# Sheet0-mcu.net
KiCad netlist of a schematic drawn in Altium Designer
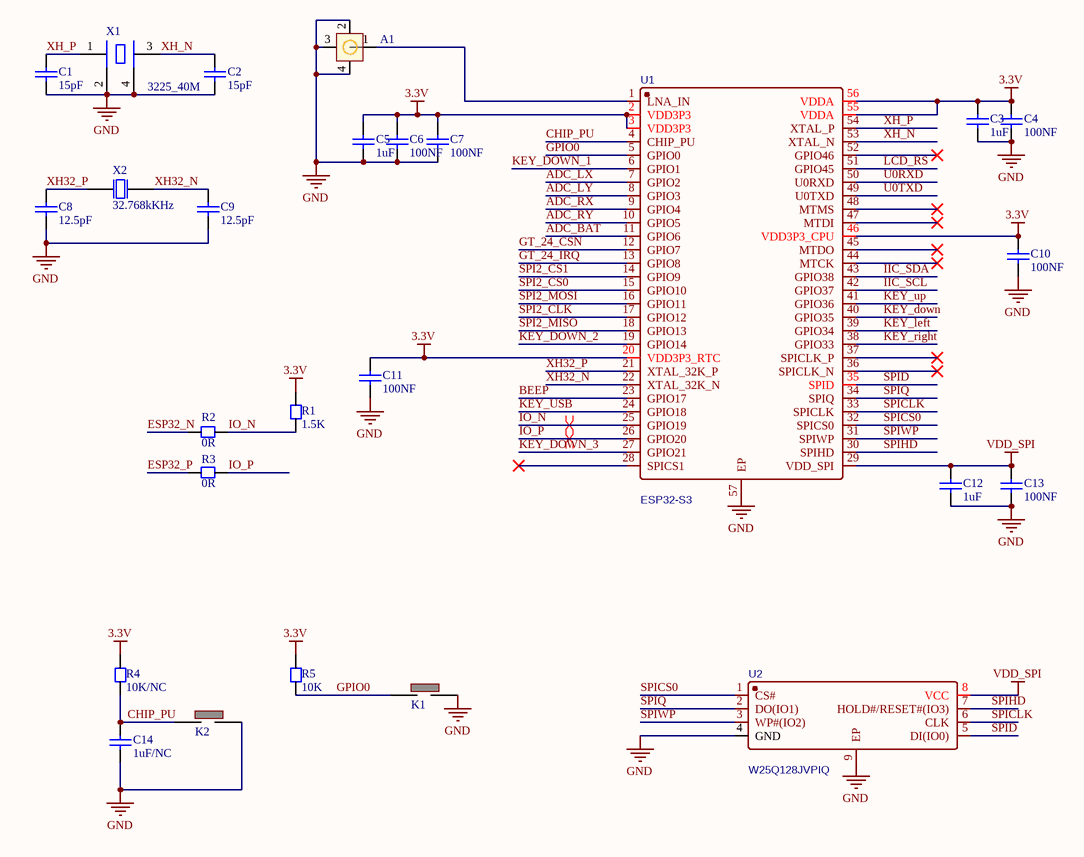
[diagram p0: Sheet0-mcu.SchDoc]

(export (version "E")
  (design (tool "Eeschema 10.0.6"))
  (components
    (comp (ref "A1")
      (value "ANT-IPEX")
      (footprint "IPEX-SMD_HC-RF-IPEX0303-01")
      (description "贴片封装的天线 封装类型为IPEX")
      (libsource (lib "antenna") (part "ANT-IPEX"))
    )
    (comp (ref "C1")
      (value "15pF")
      (footprint "CC1608-0603")
      (description "0603封装的电容")
      (fields (field (name "PUBLISHER") "Altium Limited"))
      (libsource (lib "base") (part "Cap Chip 0603"))
    )
    (comp (ref "C2")
      (value "15pF")
      (footprint "CC1608-0603")
      (description "0603封装的电容")
      (fields (field (name "PUBLISHER") "Altium Limited"))
      (libsource (lib "base") (part "Cap Chip 0603"))
    )
    (comp (ref "C3")
      (value "1uF")
      (footprint "CC1608-0603")
      (description "0603封装的电容")
      (fields (field (name "PUBLISHER") "Altium Limited"))
      (libsource (lib "base") (part "Cap Chip 0603"))
    )
    (comp (ref "C4")
      (value "100NF")
      (footprint "CC1608-0603")
      (description "0603封装的电容")
      (fields (field (name "PUBLISHER") "Altium Limited"))
      (libsource (lib "base") (part "Cap Chip 0603"))
    )
    (comp (ref "C5")
      (value "1uF")
      (footprint "CC1608-0603")
      (description "0603封装的电容")
      (fields (field (name "PUBLISHER") "Altium Limited"))
      (libsource (lib "base") (part "Cap Chip 0603"))
    )
    (comp (ref "C6")
      (value "100NF")
      (footprint "CC1608-0603")
      (description "0603封装的电容")
      (fields (field (name "PUBLISHER") "Altium Limited"))
      (libsource (lib "base") (part "Cap Chip 0603"))
    )
    (comp (ref "C7")
      (value "100NF")
      (footprint "CC1608-0603")
      (description "0603封装的电容")
      (fields (field (name "PUBLISHER") "Altium Limited"))
      (libsource (lib "base") (part "Cap Chip 0603"))
    )
    (comp (ref "C8")
      (value "12.5pF")
      (footprint "CC1608-0603")
      (description "0603封装的电容")
      (fields (field (name "PUBLISHER") "Altium Limited"))
      (libsource (lib "base") (part "Cap Chip 0603"))
    )
    (comp (ref "C9")
      (value "12.5pF")
      (footprint "CC1608-0603")
      (description "0603封装的电容")
      (fields (field (name "PUBLISHER") "Altium Limited"))
      (libsource (lib "base") (part "Cap Chip 0603"))
    )
    (comp (ref "C10")
      (value "100NF")
      (footprint "CC1608-0603")
      (description "0603封装的电容")
      (fields (field (name "PUBLISHER") "Altium Limited"))
      (libsource (lib "base") (part "Cap Chip 0603"))
    )
    (comp (ref "C11")
      (value "100NF")
      (footprint "CC1608-0603")
      (description "0603封装的电容")
      (fields (field (name "PUBLISHER") "Altium Limited"))
      (libsource (lib "base") (part "Cap Chip 0603"))
    )
    (comp (ref "C12")
      (value "1uF")
      (footprint "CC1608-0603")
      (description "0603封装的电容")
      (fields (field (name "PUBLISHER") "Altium Limited"))
      (libsource (lib "base") (part "Cap Chip 0603"))
    )
    (comp (ref "C13")
      (value "100NF")
      (footprint "CC1608-0603")
      (description "0603封装的电容")
      (fields (field (name "PUBLISHER") "Altium Limited"))
      (libsource (lib "base") (part "Cap Chip 0603"))
    )
    (comp (ref "C14")
      (value "1uF/NC")
      (footprint "CC1608-0603")
      (description "0603封装的电容")
      (fields (field (name "PUBLISHER") "Altium Limited"))
      (libsource (lib "base") (part "Cap Chip 0603"))
    )
    (comp (ref "K1")
      (value "KEY 3*4")
      (footprint "KEY 3*4")
      (description "轻触开关按键")
      (libsource (lib "base") (part "KEY 3*4"))
    )
    (comp (ref "K2")
      (value "KEY 3*4")
      (footprint "KEY 3*4")
      (description "轻触开关按键")
      (libsource (lib "base") (part "KEY 3*4"))
    )
    (comp (ref "R1")
      (value "1.5K")
      (footprint "CR1608-0603")
      (description "0603封装电阻")
      (fields (field (name "PUBLISHER") "Altium Limited"))
      (libsource (lib "") (part "Resistor Chip 0603_2"))
    )
    (comp (ref "R2")
      (value "0R")
      (footprint "CR1608-0603")
      (description "0603封装电阻")
      (fields (field (name "PUBLISHER") "Altium Limited"))
      (libsource (lib "base") (part "Resistor Chip 0603"))
    )
    (comp (ref "R3")
      (value "0R")
      (footprint "CR1608-0603")
      (description "0603封装电阻")
      (fields (field (name "PUBLISHER") "Altium Limited"))
      (libsource (lib "base") (part "Resistor Chip 0603"))
    )
    (comp (ref "R4")
      (value "10K/NC")
      (footprint "CR1608-0603")
      (description "0603封装电阻")
      (fields (field (name "PUBLISHER") "Altium Limited"))
      (libsource (lib "") (part "Resistor Chip 0603_1"))
    )
    (comp (ref "R5")
      (value "10K")
      (footprint "CR1608-0603")
      (description "0603封装电阻")
      (fields (field (name "PUBLISHER") "Altium Limited"))
      (libsource (lib "") (part "Resistor Chip 0603_1"))
    )
    (comp (ref "U1")
      (value "ESP32-S3")
      (footprint "QFN-56")
      (fields (field (name "MANUFACTURER") "ESPRESSIF(乐鑫)") (field (name "CONTRIBUTOR") "LCSC"))
      (libsource (lib "singlechip") (part "ESP32-S3"))
    )
    (comp (ref "U2")
      (value "W25Q128JVPIQ")
      (footprint "WSON-8")
      (fields (field (name "MANUFACTURER") "WINBOND(华邦)") (field (name "CONTRIBUTOR") "LCSC"))
      (libsource (lib "PB-Chip") (part "W25Q128JVPIQ"))
    )
    (comp (ref "X1")
      (value "3225_40M")
      (footprint "XTAL-3225")
      (description "3225封装的晶振")
      (libsource (lib "base") (part "XTAL 3225"))
    )
    (comp (ref "X2")
      (value "32.768kKHz")
      (footprint "XTAL-3215")
      (description "3215封装的时钟晶振")
      (libsource (lib "base") (part "XTAL 3215 32.768kKHz"))
    )
  )
  (nets
    (net (code "1") (name "/ADC_BAT") (class "Default")
      (node (ref "U1") (pin "11") (pinfunction "GPIO6_11") (pintype "passive"))
    )
    (net (code "2") (name "/ADC_LX") (class "Default")
      (node (ref "U1") (pin "7") (pinfunction "GPIO2_7") (pintype "passive"))
    )
    (net (code "3") (name "/ADC_LY") (class "Default")
      (node (ref "U1") (pin "8") (pinfunction "GPIO3_8") (pintype "passive"))
    )
    (net (code "4") (name "/ADC_RX") (class "Default")
      (node (ref "U1") (pin "9") (pinfunction "GPIO4_9") (pintype "passive"))
    )
    (net (code "5") (name "/ADC_RY") (class "Default")
      (node (ref "U1") (pin "10") (pinfunction "GPIO5_10") (pintype "passive"))
    )
    (net (code "6") (name "/BEEP") (class "Default")
      (node (ref "U1") (pin "23") (pinfunction "GPIO17_23") (pintype "passive"))
    )
    (net (code "7") (name "/CHIP_PU") (class "Default")
      (node (ref "C14") (pin "2") (pinfunction "2_2") (pintype "passive"))
      (node (ref "K2") (pin "1") (pinfunction "1_1") (pintype "passive"))
      (node (ref "R4") (pin "1") (pinfunction "1_1") (pintype "passive"))
      (node (ref "U1") (pin "4") (pinfunction "CHIP_PU_4") (pintype "passive"))
    )
    (net (code "8") (name "/ESP32_N") (class "Default")
      (node (ref "R2") (pin "2") (pinfunction "2_2") (pintype "passive"))
    )
    (net (code "9") (name "/ESP32_P") (class "Default")
      (node (ref "R3") (pin "2") (pinfunction "2_2") (pintype "passive"))
    )
    (net (code "10") (name "/GPIO0") (class "Default")
      (node (ref "K1") (pin "1") (pinfunction "1_1") (pintype "passive"))
      (node (ref "R5") (pin "1") (pinfunction "1_1") (pintype "passive"))
      (node (ref "U1") (pin "5") (pinfunction "GPIO0_5") (pintype "passive"))
    )
    (net (code "11") (name "/GT_24_CSN") (class "Default")
      (node (ref "U1") (pin "12") (pinfunction "GPIO7_12") (pintype "passive"))
    )
    (net (code "12") (name "/GT_24_IRQ") (class "Default")
      (node (ref "U1") (pin "13") (pinfunction "GPIO8_13") (pintype "passive"))
    )
    (net (code "13") (name "/IIC_SCL") (class "Default")
      (node (ref "U1") (pin "42") (pinfunction "GPIO37_42") (pintype "passive"))
    )
    (net (code "14") (name "/IIC_SDA") (class "Default")
      (node (ref "U1") (pin "43") (pinfunction "GPIO38_43") (pintype "passive"))
    )
    (net (code "15") (name "/IO_N") (class "Default")
      (node (ref "R1") (pin "2") (pinfunction "2_2") (pintype "passive"))
      (node (ref "R2") (pin "1") (pinfunction "1_1") (pintype "passive"))
      (node (ref "U1") (pin "25") (pinfunction "GPIO19_25") (pintype "passive"))
    )
    (net (code "16") (name "/IO_P") (class "Default")
      (node (ref "R3") (pin "1") (pinfunction "1_1") (pintype "passive"))
      (node (ref "U1") (pin "26") (pinfunction "GPIO20_26") (pintype "passive"))
    )
    (net (code "17") (name "/KEY_DOWN_1") (class "Default")
      (node (ref "U1") (pin "6") (pinfunction "GPIO1_6") (pintype "passive"))
    )
    (net (code "18") (name "/KEY_DOWN_2") (class "Default")
      (node (ref "U1") (pin "19") (pinfunction "GPIO14_19") (pintype "passive"))
    )
    (net (code "19") (name "/KEY_DOWN_3") (class "Default")
      (node (ref "U1") (pin "27") (pinfunction "GPIO21_27") (pintype "passive"))
    )
    (net (code "20") (name "/KEY_USB") (class "Default")
      (node (ref "U1") (pin "24") (pinfunction "GPIO18_24") (pintype "passive"))
    )
    (net (code "21") (name "/KEY_down") (class "Default")
      (node (ref "U1") (pin "40") (pinfunction "GPIO35_40") (pintype "passive"))
    )
    (net (code "22") (name "/KEY_left") (class "Default")
      (node (ref "U1") (pin "39") (pinfunction "GPIO34_39") (pintype "passive"))
    )
    (net (code "23") (name "/KEY_right") (class "Default")
      (node (ref "U1") (pin "38") (pinfunction "GPIO33_38") (pintype "passive"))
    )
    (net (code "24") (name "/KEY_up") (class "Default")
      (node (ref "U1") (pin "41") (pinfunction "GPIO36_41") (pintype "passive"))
    )
    (net (code "25") (name "/LCD_RS") (class "Default")
      (node (ref "U1") (pin "51") (pinfunction "GPIO45_51") (pintype "passive"))
    )
    (net (code "26") (name "/SPI2_CLK") (class "Default")
      (node (ref "U1") (pin "17") (pinfunction "GPIO12_17") (pintype "passive"))
    )
    (net (code "27") (name "/SPI2_CS0") (class "Default")
      (node (ref "U1") (pin "15") (pinfunction "GPIO10_15") (pintype "passive"))
    )
    (net (code "28") (name "/SPI2_CS1") (class "Default")
      (node (ref "U1") (pin "14") (pinfunction "GPIO9_14") (pintype "passive"))
    )
    (net (code "29") (name "/SPI2_MISO") (class "Default")
      (node (ref "U1") (pin "18") (pinfunction "GPIO13_18") (pintype "passive"))
    )
    (net (code "30") (name "/SPI2_MOSI") (class "Default")
      (node (ref "U1") (pin "16") (pinfunction "GPIO11_16") (pintype "passive"))
    )
    (net (code "31") (name "/SPICLK") (class "Default")
      (node (ref "U1") (pin "33") (pinfunction "SPICLK_33") (pintype "passive"))
      (node (ref "U2") (pin "6") (pinfunction "CLK_6") (pintype "passive"))
    )
    (net (code "32") (name "/SPICS0") (class "Default")
      (node (ref "U1") (pin "32") (pinfunction "SPICS0_32") (pintype "passive"))
      (node (ref "U2") (pin "1") (pinfunction "CS#_1") (pintype "passive"))
    )
    (net (code "33") (name "/SPID") (class "Default")
      (node (ref "U1") (pin "35") (pinfunction "SPID_35") (pintype "passive"))
      (node (ref "U2") (pin "5") (pinfunction "DI(IO0)_5") (pintype "passive"))
    )
    (net (code "34") (name "/SPIHD") (class "Default")
      (node (ref "U1") (pin "30") (pinfunction "SPIHD_30") (pintype "passive"))
      (node (ref "U2") (pin "7") (pinfunction "HOLD#/RESET#(IO3)_7") (pintype "passive"))
    )
    (net (code "35") (name "/SPIQ") (class "Default")
      (node (ref "U1") (pin "34") (pinfunction "SPIQ_34") (pintype "passive"))
      (node (ref "U2") (pin "2") (pinfunction "DO(IO1)_2") (pintype "passive"))
    )
    (net (code "36") (name "/SPIWP") (class "Default")
      (node (ref "U1") (pin "31") (pinfunction "SPIWP_31") (pintype "passive"))
      (node (ref "U2") (pin "3") (pinfunction "WP#(IO2)_3") (pintype "passive"))
    )
    (net (code "37") (name "/U0RXD") (class "Default")
      (node (ref "U1") (pin "50") (pinfunction "U0RXD_50") (pintype "passive"))
    )
    (net (code "38") (name "/U0TXD") (class "Default")
      (node (ref "U1") (pin "49") (pinfunction "U0TXD_49") (pintype "passive"))
    )
    (net (code "39") (name "/XH32_N") (class "Default")
      (node (ref "C9") (pin "2") (pinfunction "2_2") (pintype "passive"))
      (node (ref "U1") (pin "22") (pinfunction "XTAL_32K_N_22") (pintype "passive"))
      (node (ref "X2") (pin "2") (pinfunction "OSC2_2") (pintype "passive"))
    )
    (net (code "40") (name "/XH32_P") (class "Default")
      (node (ref "C8") (pin "2") (pinfunction "2_2") (pintype "passive"))
      (node (ref "U1") (pin "21") (pinfunction "XTAL_32K_P_21") (pintype "passive"))
      (node (ref "X2") (pin "1") (pinfunction "OSC1_1") (pintype "passive"))
    )
    (net (code "41") (name "/XH_N") (class "Default")
      (node (ref "C2") (pin "2") (pinfunction "2_2") (pintype "passive"))
      (node (ref "U1") (pin "53") (pinfunction "XTAL_N_53") (pintype "passive"))
      (node (ref "X1") (pin "3") (pinfunction "OSC2_3") (pintype "passive"))
    )
    (net (code "42") (name "/XH_P") (class "Default")
      (node (ref "C1") (pin "2") (pinfunction "2_2") (pintype "passive"))
      (node (ref "U1") (pin "54") (pinfunction "XTAL_P_54") (pintype "passive"))
      (node (ref "X1") (pin "1") (pinfunction "OSC1_1") (pintype "passive"))
    )
    (net (code "43") (name "3.3V") (class "Default")
      (node (ref "C10") (pin "2") (pinfunction "2_2") (pintype "passive"))
      (node (ref "C11") (pin "2") (pinfunction "2_2") (pintype "passive"))
      (node (ref "C3") (pin "2") (pinfunction "2_2") (pintype "passive"))
      (node (ref "C4") (pin "2") (pinfunction "2_2") (pintype "passive"))
      (node (ref "C5") (pin "2") (pinfunction "2_2") (pintype "passive"))
      (node (ref "C6") (pin "2") (pinfunction "2_2") (pintype "passive"))
      (node (ref "C7") (pin "2") (pinfunction "2_2") (pintype "passive"))
      (node (ref "R1") (pin "1") (pinfunction "1_1") (pintype "passive"))
      (node (ref "R4") (pin "2") (pinfunction "2_2") (pintype "passive"))
      (node (ref "R5") (pin "2") (pinfunction "2_2") (pintype "passive"))
      (node (ref "U1") (pin "2") (pinfunction "VDD3P3_2") (pintype "passive"))
      (node (ref "U1") (pin "20") (pinfunction "VDD3P3_RTC_20") (pintype "passive"))
      (node (ref "U1") (pin "3") (pinfunction "VDD3P3_3") (pintype "passive"))
      (node (ref "U1") (pin "46") (pinfunction "VDD3P3_CPU_46") (pintype "passive"))
      (node (ref "U1") (pin "55") (pinfunction "VDDA_55") (pintype "passive"))
      (node (ref "U1") (pin "56") (pinfunction "VDDA_56") (pintype "passive"))
    )
    (net (code "44") (name "GND") (class "Default")
      (node (ref "A1") (pin "2") (pinfunction "2_2") (pintype "passive"))
      (node (ref "A1") (pin "3") (pinfunction "3_3") (pintype "passive"))
      (node (ref "A1") (pin "4") (pinfunction "4_4") (pintype "passive"))
      (node (ref "C1") (pin "1") (pinfunction "1_1") (pintype "passive"))
      (node (ref "C10") (pin "1") (pinfunction "1_1") (pintype "passive"))
      (node (ref "C11") (pin "1") (pinfunction "1_1") (pintype "passive"))
      (node (ref "C12") (pin "1") (pinfunction "1_1") (pintype "passive"))
      (node (ref "C13") (pin "1") (pinfunction "1_1") (pintype "passive"))
      (node (ref "C14") (pin "1") (pinfunction "1_1") (pintype "passive"))
      (node (ref "C2") (pin "1") (pinfunction "1_1") (pintype "passive"))
      (node (ref "C3") (pin "1") (pinfunction "1_1") (pintype "passive"))
      (node (ref "C4") (pin "1") (pinfunction "1_1") (pintype "passive"))
      (node (ref "C5") (pin "1") (pinfunction "1_1") (pintype "passive"))
      (node (ref "C6") (pin "1") (pinfunction "1_1") (pintype "passive"))
      (node (ref "C7") (pin "1") (pinfunction "1_1") (pintype "passive"))
      (node (ref "C8") (pin "1") (pinfunction "1_1") (pintype "passive"))
      (node (ref "C9") (pin "1") (pinfunction "1_1") (pintype "passive"))
      (node (ref "K1") (pin "2") (pinfunction "2_2") (pintype "passive"))
      (node (ref "K2") (pin "2") (pinfunction "2_2") (pintype "passive"))
      (node (ref "U1") (pin "57") (pinfunction "EP_57") (pintype "passive"))
      (node (ref "U2") (pin "4") (pinfunction "GND_4") (pintype "passive"))
      (node (ref "U2") (pin "9") (pinfunction "EP_9") (pintype "passive"))
      (node (ref "X1") (pin "2") (pinfunction "GND_2") (pintype "passive"))
      (node (ref "X1") (pin "4") (pinfunction "GND_4") (pintype "passive"))
    )
    (net (code "45") (name "Net-(U1-LNA_IN)") (class "Default")
      (node (ref "A1") (pin "1") (pinfunction "1_1") (pintype "passive"))
      (node (ref "U1") (pin "1") (pinfunction "LNA_IN_1") (pintype "passive"))
    )
    (net (code "46") (name "VDD_SPI") (class "Default")
      (node (ref "C12") (pin "2") (pinfunction "2_2") (pintype "passive"))
      (node (ref "C13") (pin "2") (pinfunction "2_2") (pintype "passive"))
      (node (ref "U1") (pin "29") (pinfunction "VDD_SPI_29") (pintype "passive"))
      (node (ref "U2") (pin "8") (pinfunction "VCC_8") (pintype "passive"))
    )
    (net (code "47") (name "unconnected-(U1-GPIO46-Pad52)") (class "Default")
      (node (ref "U1") (pin "52") (pinfunction "GPIO46_52") (pintype "passive+no_connect"))
    )
    (net (code "48") (name "unconnected-(U1-MTCK-Pad44)") (class "Default")
      (node (ref "U1") (pin "44") (pinfunction "MTCK_44") (pintype "passive+no_connect"))
    )
    (net (code "49") (name "unconnected-(U1-MTDI-Pad47)") (class "Default")
      (node (ref "U1") (pin "47") (pinfunction "MTDI_47") (pintype "passive+no_connect"))
    )
    (net (code "50") (name "unconnected-(U1-MTDO-Pad45)") (class "Default")
      (node (ref "U1") (pin "45") (pinfunction "MTDO_45") (pintype "passive+no_connect"))
    )
    (net (code "51") (name "unconnected-(U1-MTMS-Pad48)") (class "Default")
      (node (ref "U1") (pin "48") (pinfunction "MTMS_48") (pintype "passive+no_connect"))
    )
    (net (code "52") (name "unconnected-(U1-SPICLK_N-Pad36)") (class "Default")
      (node (ref "U1") (pin "36") (pinfunction "SPICLK_N_36") (pintype "passive+no_connect"))
    )
    (net (code "53") (name "unconnected-(U1-SPICLK_P-Pad37)") (class "Default")
      (node (ref "U1") (pin "37") (pinfunction "SPICLK_P_37") (pintype "passive+no_connect"))
    )
    (net (code "54") (name "unconnected-(U1-SPICS1-Pad28)") (class "Default")
      (node (ref "U1") (pin "28") (pinfunction "SPICS1_28") (pintype "passive+no_connect"))
    )
  )
)
